# 3PDT_Buffer_Board.net
KiCad netlist of a schematic drawn in EAGLE
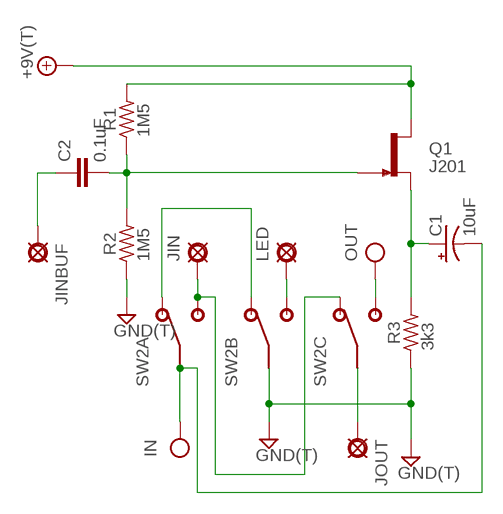
[diagram p0: schematic, sheet 1]

(export (version "E")
  (design (tool "Eeschema 10.0.6"))
  (components
    (comp (ref "+9V")
      (value "+9V(T)")
      (footprint "eagle-import:SQUARE")
      (libsource (lib "eagle-import") (part "+9V(T)"))
    )
    (comp (ref "C1")
      (value "10uF")
      (footprint "eagle-import:050_020_1")
      (libsource (lib "eagle-import") (part "0501"))
    )
    (comp (ref "C2")
      (value "0.1uF")
      (footprint "eagle-import:080X050")
      (libsource (lib "eagle-import") (part "080X0502"))
    )
    (comp (ref "G")
      (value "GND(T)")
      (footprint "eagle-import:SQUARE")
      (libsource (lib "eagle-import") (part "GND(T)"))
    )
    (comp (ref "IN")
      (value "IN(T)")
      (footprint "eagle-import:SQUARE")
      (libsource (lib "eagle-import") (part "IN(T)"))
    )
    (comp (ref "JIG")
      (value "GND(T)")
      (footprint "eagle-import:SQUARE")
      (libsource (lib "eagle-import") (part "GND(T)"))
    )
    (comp (ref "JIN")
      (value "PAD")
      (footprint "eagle-import:SQUARE")
      (libsource (lib "eagle-import") (part "PAD"))
    )
    (comp (ref "JINBUF")
      (value "PAD")
      (footprint "eagle-import:SQUARE")
      (libsource (lib "eagle-import") (part "PAD"))
    )
    (comp (ref "JOG")
      (value "GND(T)")
      (footprint "eagle-import:SQUARE")
      (libsource (lib "eagle-import") (part "GND(T)"))
    )
    (comp (ref "JOUT")
      (value "PAD")
      (footprint "eagle-import:SQUARE")
      (libsource (lib "eagle-import") (part "PAD"))
    )
    (comp (ref "LED")
      (value "PAD")
      (footprint "eagle-import:SQUARE")
      (libsource (lib "eagle-import") (part "PAD"))
    )
    (comp (ref "OUT")
      (value "OUT(T)")
      (footprint "eagle-import:SQUARE")
      (libsource (lib "eagle-import") (part "OUT(T)"))
    )
    (comp (ref "Q1")
      (value "J201")
      (footprint "eagle-import:TO92-")
      (libsource (lib "eagle-import") (part "J201"))
    )
    (comp (ref "R1")
      (value "1M5")
      (footprint "eagle-import:R0207_3")
      (libsource (lib "eagle-import") (part "6MM.3"))
    )
    (comp (ref "R2")
      (value "1M5")
      (footprint "eagle-import:R0207_3")
      (libsource (lib "eagle-import") (part "6MM.3"))
    )
    (comp (ref "R3")
      (value "3k3")
      (footprint "eagle-import:R0207_3")
      (libsource (lib "eagle-import") (part "6MM.3"))
    )
    (comp (ref "SW2")
      (value "3PDT")
      (footprint "eagle-import:3PDT")
      (libsource (lib "eagle-import") (part "3PDT"))
    )
  )
  (nets
    (net (code "1") (name "+9V(T)") (class "Default")
      (node (ref "+9V") (pin "1") (pinfunction "+9V_1") (pintype "power_in"))
      (node (ref "Q1") (pin "3") (pinfunction "D_3") (pintype "passive"))
      (node (ref "R1") (pin "2") (pinfunction "2_2") (pintype "passive"))
    )
    (net (code "2") (name "GND(T)") (class "Default")
      (node (ref "G") (pin "1") (pinfunction "GND_1") (pintype "power_in"))
      (node (ref "JIG") (pin "1") (pinfunction "GND_1") (pintype "power_in"))
      (node (ref "JOG") (pin "1") (pinfunction "GND_1") (pintype "power_in"))
      (node (ref "R2") (pin "1") (pinfunction "1_1") (pintype "passive"))
      (node (ref "R3") (pin "1") (pinfunction "1_1") (pintype "passive"))
      (node (ref "SW2") (pin "B2") (pinfunction "2_B2") (pintype "passive"))
    )
    (net (code "3") (name "IN(T)") (class "Default")
      (node (ref "C1") (pin "-") (pinfunction "-_-") (pintype "passive"))
      (node (ref "IN") (pin "1") (pinfunction "IN_1") (pintype "power_in"))
      (node (ref "SW2") (pin "A2") (pinfunction "2_A2") (pintype "passive"))
    )
    (net (code "4") (name "Net-(JIN-PAD)") (class "Default")
      (node (ref "JIN") (pin "1") (pinfunction "PAD_1") (pintype "passive"))
      (node (ref "SW2") (pin "A3") (pinfunction "3_A3") (pintype "passive"))
      (node (ref "SW2") (pin "C1") (pinfunction "1_C1") (pintype "passive"))
    )
    (net (code "5") (name "Net-(JINBUF-PAD)") (class "Default")
      (node (ref "C2") (pin "1") (pinfunction "1_1") (pintype "passive"))
      (node (ref "JINBUF") (pin "1") (pinfunction "PAD_1") (pintype "passive"))
    )
    (net (code "6") (name "Net-(JOUT-PAD)") (class "Default")
      (node (ref "JOUT") (pin "1") (pinfunction "PAD_1") (pintype "passive"))
      (node (ref "SW2") (pin "C2") (pinfunction "2_C2") (pintype "passive"))
    )
    (net (code "7") (name "Net-(LED-PAD)") (class "Default")
      (node (ref "LED") (pin "1") (pinfunction "PAD_1") (pintype "passive"))
      (node (ref "SW2") (pin "B3") (pinfunction "3_B3") (pintype "passive"))
    )
    (net (code "8") (name "Net-(Q1-G)") (class "Default")
      (node (ref "C2") (pin "2") (pinfunction "2_2") (pintype "passive"))
      (node (ref "Q1") (pin "1") (pinfunction "G_1") (pintype "passive"))
      (node (ref "R1") (pin "1") (pinfunction "1_1") (pintype "passive"))
      (node (ref "R2") (pin "2") (pinfunction "2_2") (pintype "passive"))
    )
    (net (code "9") (name "Net-(Q1-S)") (class "Default")
      (node (ref "C1") (pin "+") (pinfunction "+_+") (pintype "passive"))
      (node (ref "Q1") (pin "2") (pinfunction "S_2") (pintype "passive"))
      (node (ref "R3") (pin "2") (pinfunction "2_2") (pintype "passive"))
    )
    (net (code "10") (name "Net-(SW2A-1)") (class "Default")
      (node (ref "SW2") (pin "A1") (pinfunction "1_A1") (pintype "passive"))
      (node (ref "SW2") (pin "B1") (pinfunction "1_B1") (pintype "passive"))
    )
    (net (code "11") (name "OUT(T)") (class "Default")
      (node (ref "OUT") (pin "1") (pinfunction "OUT_1") (pintype "power_in"))
      (node (ref "SW2") (pin "C3") (pinfunction "3_C3") (pintype "passive"))
    )
  )
)
